# SB_TS_0_53.net
KiCad netlist of a schematic drawn in EAGLE
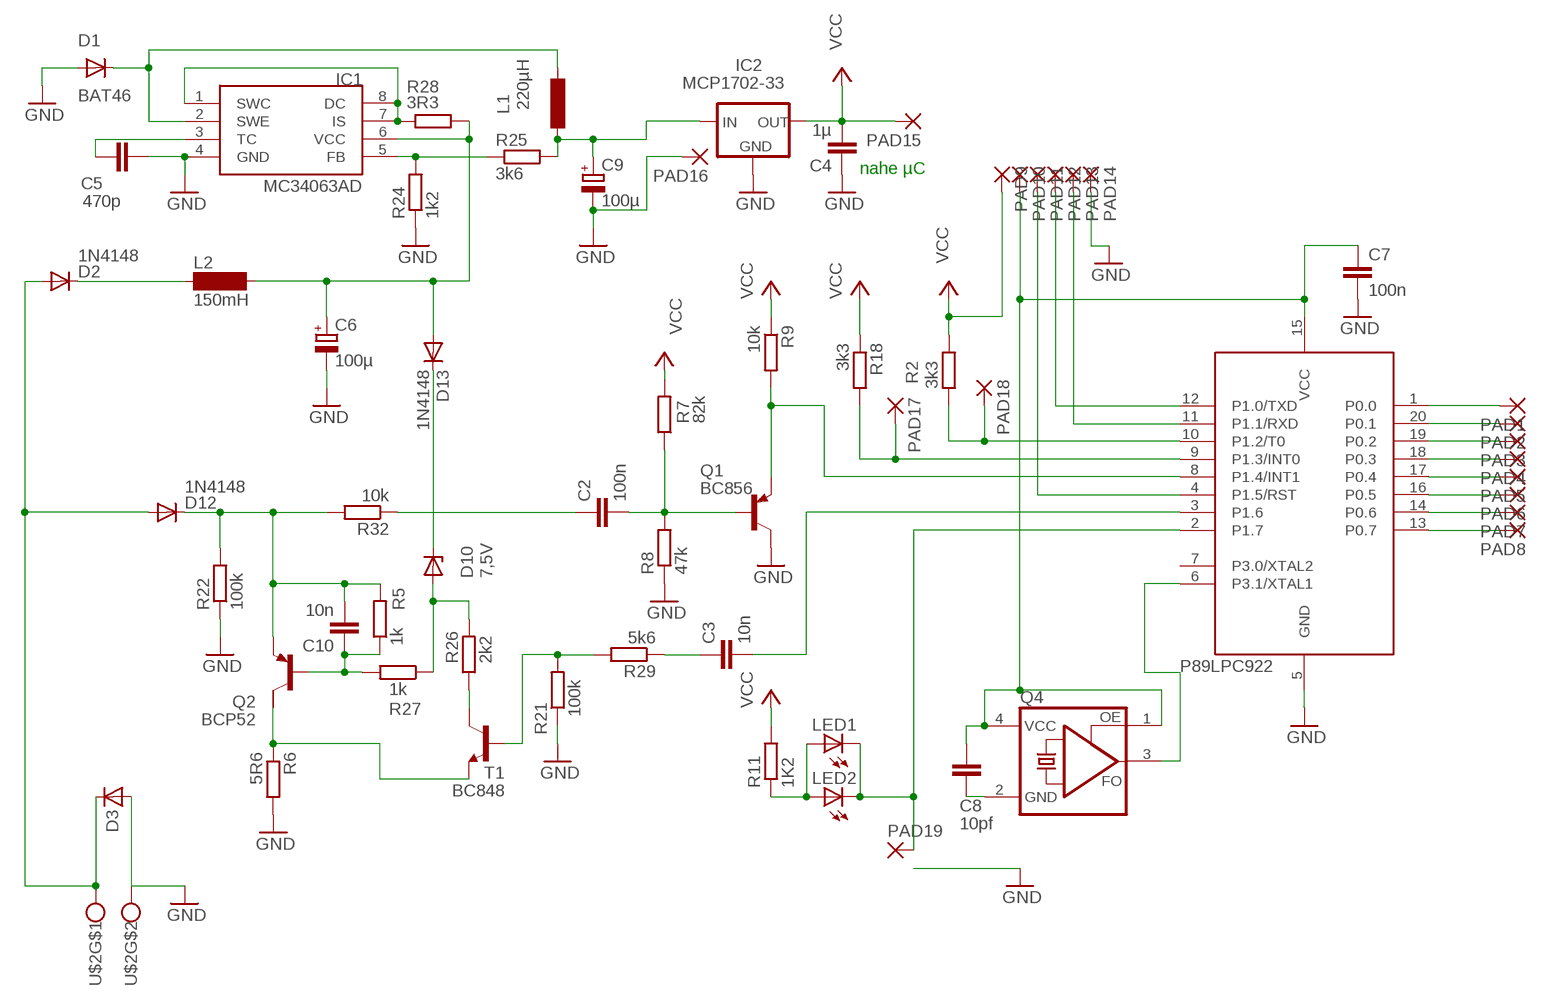
[diagram p0: schematic, sheet 1]

(export (version "E")
  (design (tool "Eeschema 10.0.6"))
  (components
    (comp (ref "C2")
      (value "100n")
      (footprint "eagle-import:C1206")
      (libsource (lib "eagle-import") (part "C-EUC1206"))
    )
    (comp (ref "C3")
      (value "10n")
      (footprint "eagle-import:C1206")
      (libsource (lib "eagle-import") (part "C-EUC1206"))
    )
    (comp (ref "C4")
      (value "1µ")
      (footprint "eagle-import:C1206")
      (libsource (lib "eagle-import") (part "C-EUC1206"))
    )
    (comp (ref "C5")
      (value "470p")
      (footprint "eagle-import:C1206")
      (libsource (lib "eagle-import") (part "C-EUC1206"))
    )
    (comp (ref "C6")
      (value "100µ")
      (footprint "eagle-import:E5-8,5")
      (libsource (lib "eagle-import") (part "CPOL-EUE5-8.5"))
    )
    (comp (ref "C7")
      (value "100n")
      (footprint "eagle-import:C1206")
      (libsource (lib "eagle-import") (part "C-EUC1206"))
    )
    (comp (ref "C8")
      (value "10pf")
      (footprint "eagle-import:C1206")
      (libsource (lib "eagle-import") (part "C-EUC1206"))
    )
    (comp (ref "C9")
      (value "100µ")
      (footprint "eagle-import:E2,5-5")
      (libsource (lib "eagle-import") (part "CPOL-EUE2.5-5"))
    )
    (comp (ref "C10")
      (value "10n")
      (footprint "eagle-import:C1206")
      (libsource (lib "eagle-import") (part "C-EUC1206"))
    )
    (comp (ref "D1")
      (value "BAT46")
      (footprint "eagle-import:MINIMELF")
      (libsource (lib "eagle-import") (part "DIODE-MINIMELF"))
    )
    (comp (ref "D2")
      (value "1N4148")
      (footprint "eagle-import:MINIMELF")
      (libsource (lib "eagle-import") (part "DIODE-MINIMELF"))
    )
    (comp (ref "D3")
      (value "SMAJ40AC")
      (footprint "eagle-import:SMB")
      (libsource (lib "eagle-import") (part "D-SMB"))
    )
    (comp (ref "D10")
      (value "7,5V")
      (footprint "eagle-import:MINIMELF")
      (libsource (lib "eagle-import") (part "ZPD"))
    )
    (comp (ref "D12")
      (value "1N4148")
      (footprint "eagle-import:MINIMELF")
      (libsource (lib "eagle-import") (part "DIODE-MINIMELF"))
    )
    (comp (ref "D13")
      (value "1N4148")
      (footprint "eagle-import:MINIMELF")
      (libsource (lib "eagle-import") (part "DIODE-MINIMELF"))
    )
    (comp (ref "IC1")
      (value "MC34063AD")
      (footprint "eagle-import:SOIC8")
      (libsource (lib "eagle-import") (part "MC34063AD"))
    )
    (comp (ref "IC2")
      (value "MCP1702-33")
      (footprint "eagle-import:79LXX")
      (libsource (lib "eagle-import") (part "79LXX"))
    )
    (comp (ref "L1")
      (value "220µH")
      (footprint "eagle-import:2200-11.43")
      (libsource (lib "eagle-import") (part "L-EU2200-11.43"))
    )
    (comp (ref "L2")
      (value "150mH")
      (footprint "eagle-import:SD12_1000")
      (libsource (lib "eagle-import") (part "SD12-1000"))
    )
    (comp (ref "LED1")
      (value "LEDCHIPLED_1206")
      (footprint "eagle-import:CHIPLED_1206")
      (libsource (lib "eagle-import") (part "LEDCHIPLED_1206"))
    )
    (comp (ref "LED2")
      (value "LED3MM")
      (footprint "eagle-import:LED3MM")
      (libsource (lib "eagle-import") (part "LED3MM"))
    )
    (comp (ref "PAD1")
      (value "SMD2")
      (footprint "eagle-import:SMD1,27-2,54")
      (libsource (lib "eagle-import") (part "SMD2"))
    )
    (comp (ref "PAD2")
      (value "SMD2")
      (footprint "eagle-import:SMD1,27-2,54")
      (libsource (lib "eagle-import") (part "SMD2"))
    )
    (comp (ref "PAD3")
      (value "SMD2")
      (footprint "eagle-import:SMD1,27-2,54")
      (libsource (lib "eagle-import") (part "SMD2"))
    )
    (comp (ref "PAD4")
      (value "SMD2")
      (footprint "eagle-import:SMD1,27-2,54")
      (libsource (lib "eagle-import") (part "SMD2"))
    )
    (comp (ref "PAD5")
      (value "SMD2")
      (footprint "eagle-import:SMD1,27-2,54")
      (libsource (lib "eagle-import") (part "SMD2"))
    )
    (comp (ref "PAD6")
      (value "SMD2")
      (footprint "eagle-import:SMD1,27-2,54")
      (libsource (lib "eagle-import") (part "SMD2"))
    )
    (comp (ref "PAD7")
      (value "SMD2")
      (footprint "eagle-import:SMD1,27-2,54")
      (libsource (lib "eagle-import") (part "SMD2"))
    )
    (comp (ref "PAD8")
      (value "SMD2")
      (footprint "eagle-import:SMD1,27-2,54")
      (libsource (lib "eagle-import") (part "SMD2"))
    )
    (comp (ref "PAD9")
      (value "SMD2")
      (footprint "eagle-import:SMD1,27-2,54")
      (libsource (lib "eagle-import") (part "SMD2"))
    )
    (comp (ref "PAD10")
      (value "SMD2")
      (footprint "eagle-import:SMD1,27-2,54")
      (libsource (lib "eagle-import") (part "SMD2"))
    )
    (comp (ref "PAD11")
      (value "SMD2")
      (footprint "eagle-import:SMD1,27-2,54")
      (libsource (lib "eagle-import") (part "SMD2"))
    )
    (comp (ref "PAD12")
      (value "SMD2")
      (footprint "eagle-import:SMD1,27-2,54")
      (libsource (lib "eagle-import") (part "SMD2"))
    )
    (comp (ref "PAD13")
      (value "SMD2")
      (footprint "eagle-import:SMD1,27-2,54")
      (libsource (lib "eagle-import") (part "SMD2"))
    )
    (comp (ref "PAD14")
      (value "SMD2")
      (footprint "eagle-import:SMD1,27-2,54")
      (libsource (lib "eagle-import") (part "SMD2"))
    )
    (comp (ref "PAD15")
      (value "SMD2")
      (footprint "eagle-import:SMD1,27-2,54")
      (libsource (lib "eagle-import") (part "SMD2"))
    )
    (comp (ref "PAD16")
      (value "SMD2")
      (footprint "eagle-import:SMD1,27-2,54")
      (libsource (lib "eagle-import") (part "SMD2"))
    )
    (comp (ref "PAD17")
      (value "SMD2")
      (footprint "eagle-import:SMD1,27-2,54")
      (libsource (lib "eagle-import") (part "SMD2"))
    )
    (comp (ref "PAD18")
      (value "SMD2")
      (footprint "eagle-import:SMD1,27-2,54")
      (libsource (lib "eagle-import") (part "SMD2"))
    )
    (comp (ref "PAD19")
      (value "SMD2")
      (footprint "eagle-import:SMD1,27-2,54")
      (libsource (lib "eagle-import") (part "SMD2"))
    )
    (comp (ref "Q1")
      (value "BC856")
      (footprint "eagle-import:SOT23-BEC")
      (libsource (lib "eagle-import") (part "BC856SMDALT1"))
    )
    (comp (ref "Q2")
      (value "BCP52")
      (footprint "eagle-import:SOT223")
      (libsource (lib "eagle-import") (part "FZT753SMD"))
    )
    (comp (ref "Q4")
      (value "ASFL")
      (footprint "eagle-import:ASF")
      (libsource (lib "eagle-import") (part "ASFL"))
    )
    (comp (ref "R2")
      (value "3k3")
      (footprint "eagle-import:M1206")
      (libsource (lib "eagle-import") (part "R-EU_M1206"))
    )
    (comp (ref "R5")
      (value "1k")
      (footprint "eagle-import:R1206")
      (libsource (lib "eagle-import") (part "R-EU_R1206"))
    )
    (comp (ref "R6")
      (value "5R6")
      (footprint "eagle-import:R1206")
      (libsource (lib "eagle-import") (part "R-EU_R1206"))
    )
    (comp (ref "R7")
      (value "82k")
      (footprint "eagle-import:R1206")
      (libsource (lib "eagle-import") (part "R-EU_R1206"))
    )
    (comp (ref "R8")
      (value "47k")
      (footprint "eagle-import:M1206")
      (libsource (lib "eagle-import") (part "R-EU_M1206"))
    )
    (comp (ref "R9")
      (value "10k")
      (footprint "eagle-import:R1206")
      (libsource (lib "eagle-import") (part "R-EU_R1206"))
    )
    (comp (ref "R11")
      (value "1K2")
      (footprint "eagle-import:R1206")
      (libsource (lib "eagle-import") (part "R-EU_R1206"))
    )
    (comp (ref "R18")
      (value "3k3")
      (footprint "eagle-import:R1206")
      (libsource (lib "eagle-import") (part "R-EU_R1206"))
    )
    (comp (ref "R21")
      (value "100k")
      (footprint "eagle-import:R1206")
      (libsource (lib "eagle-import") (part "R-EU_R1206"))
    )
    (comp (ref "R22")
      (value "100k")
      (footprint "eagle-import:M1206")
      (libsource (lib "eagle-import") (part "R-EU_M1206"))
    )
    (comp (ref "R24")
      (value "1k2")
      (footprint "eagle-import:R1206")
      (libsource (lib "eagle-import") (part "R-EU_R1206"))
    )
    (comp (ref "R25")
      (value "3k6")
      (footprint "eagle-import:M1206")
      (libsource (lib "eagle-import") (part "R-EU_M1206"))
    )
    (comp (ref "R26")
      (value "2k2")
      (footprint "eagle-import:M1206")
      (libsource (lib "eagle-import") (part "R-EU_M1206"))
    )
    (comp (ref "R27")
      (value "1k")
      (footprint "eagle-import:R1206")
      (libsource (lib "eagle-import") (part "R-EU_R1206"))
    )
    (comp (ref "R28")
      (value "3R3")
      (footprint "eagle-import:M1206")
      (libsource (lib "eagle-import") (part "R-EU_M1206"))
    )
    (comp (ref "R29")
      (value "5k6")
      (footprint "eagle-import:R1206")
      (libsource (lib "eagle-import") (part "R-EU_R1206"))
    )
    (comp (ref "R32")
      (value "10k")
      (footprint "eagle-import:R1206")
      (libsource (lib "eagle-import") (part "R-EU_R1206"))
    )
    (comp (ref "T1")
      (value "BC848")
      (footprint "eagle-import:SOT23")
      (libsource (lib "eagle-import") (part "BC848"))
    )
    (comp (ref "U$2")
      (value "AKL059-02")
      (footprint "eagle-import:AKL3.5X2")
      (libsource (lib "eagle-import") (part "AKL059-02"))
    )
    (comp (ref "U1")
      (value "89LPC922")
      (footprint "eagle-import:DIL20")
      (libsource (lib "eagle-import") (part "89LPC922"))
    )
  )
  (nets
    (net (code "1") (name "GND") (class "Default")
      (node (ref "C4") (pin "1") (pinfunction "1_1") (pintype "passive"))
      (node (ref "C5") (pin "2") (pinfunction "2_2") (pintype "passive"))
      (node (ref "C6") (pin "-") (pinfunction "-_-") (pintype "passive"))
      (node (ref "C7") (pin "2") (pinfunction "2_2") (pintype "passive"))
      (node (ref "C9") (pin "-") (pinfunction "-_-") (pintype "passive"))
      (node (ref "D1") (pin "A") (pinfunction "A_A") (pintype "passive"))
      (node (ref "D3") (pin "2") (pinfunction "A_2") (pintype "passive"))
      (node (ref "IC1") (pin "4") (pinfunction "GND_4") (pintype "passive"))
      (node (ref "IC2") (pin "GND") (pinfunction "GND_GND") (pintype "input"))
      (node (ref "PAD14") (pin "1") (pinfunction "P_1") (pintype "passive"))
      (node (ref "PAD16") (pin "1") (pinfunction "P_1") (pintype "passive"))
      (node (ref "Q1") (pin "C") (pinfunction "C_C") (pintype "passive"))
      (node (ref "R21") (pin "1") (pinfunction "1_1") (pintype "passive"))
      (node (ref "R22") (pin "1") (pinfunction "1_1") (pintype "passive"))
      (node (ref "R24") (pin "1") (pinfunction "1_1") (pintype "passive"))
      (node (ref "R6") (pin "2") (pinfunction "2_2") (pintype "passive"))
      (node (ref "R8") (pin "1") (pinfunction "1_1") (pintype "passive"))
      (node (ref "U$2") (pin "2") (pinfunction "KL_2") (pintype "passive"))
      (node (ref "U1") (pin "5") (pinfunction "GND_5") (pintype "bidirectional"))
    )
    (net (code "2") (name "Net-(C2-Pad1)") (class "Default")
      (node (ref "C2") (pin "1") (pinfunction "1_1") (pintype "passive"))
      (node (ref "R32") (pin "1") (pinfunction "1_1") (pintype "passive"))
    )
    (net (code "3") (name "Net-(C2-Pad2)") (class "Default")
      (node (ref "C2") (pin "2") (pinfunction "2_2") (pintype "passive"))
      (node (ref "Q1") (pin "B") (pinfunction "B_B") (pintype "passive"))
      (node (ref "R7") (pin "1") (pinfunction "1_1") (pintype "passive"))
      (node (ref "R8") (pin "2") (pinfunction "2_2") (pintype "passive"))
    )
    (net (code "4") (name "Net-(C3-Pad1)") (class "Default")
      (node (ref "C3") (pin "1") (pinfunction "1_1") (pintype "passive"))
      (node (ref "R29") (pin "1") (pinfunction "1_1") (pintype "passive"))
    )
    (net (code "5") (name "Net-(C9-Pad+)") (class "Default")
      (node (ref "C9") (pin "+") (pinfunction "+_+") (pintype "passive"))
      (node (ref "IC2") (pin "IN") (pinfunction "IN_IN") (pintype "input"))
      (node (ref "L1") (pin "1") (pinfunction "1_1") (pintype "passive"))
      (node (ref "R25") (pin "2") (pinfunction "2_2") (pintype "passive"))
    )
    (net (code "6") (name "Net-(D2-PadC)") (class "Default")
      (node (ref "D2") (pin "C") (pinfunction "C_C") (pintype "passive"))
      (node (ref "L2") (pin "1") (pinfunction "1_1") (pintype "passive"))
    )
    (net (code "7") (name "Net-(D3-C)") (class "Default")
      (node (ref "D12") (pin "A") (pinfunction "A_A") (pintype "passive"))
      (node (ref "D2") (pin "A") (pinfunction "A_A") (pintype "passive"))
      (node (ref "D3") (pin "1") (pinfunction "C_1") (pintype "passive"))
      (node (ref "U$2") (pin "1") (pinfunction "KL_1") (pintype "passive"))
    )
    (net (code "8") (name "Net-(D10-PadA)") (class "Default")
      (node (ref "D10") (pin "A") (pinfunction "A_A") (pintype "passive"))
      (node (ref "R26") (pin "2") (pinfunction "2_2") (pintype "passive"))
      (node (ref "R27") (pin "1") (pinfunction "1_1") (pintype "passive"))
    )
    (net (code "9") (name "Net-(D10-PadC)") (class "Default")
      (node (ref "D10") (pin "C") (pinfunction "C_C") (pintype "passive"))
      (node (ref "D13") (pin "C") (pinfunction "C_C") (pintype "passive"))
    )
    (net (code "10") (name "Net-(IC1-DC)") (class "Default")
      (node (ref "IC1") (pin "1") (pinfunction "SWC_1") (pintype "passive"))
      (node (ref "IC1") (pin "7") (pinfunction "IS_7") (pintype "passive"))
      (node (ref "IC1") (pin "8") (pinfunction "DC_8") (pintype "passive"))
      (node (ref "R28") (pin "1") (pinfunction "1_1") (pintype "passive"))
    )
    (net (code "11") (name "Net-(IC1-FB)") (class "Default")
      (node (ref "IC1") (pin "5") (pinfunction "FB_5") (pintype "passive"))
      (node (ref "R24") (pin "2") (pinfunction "2_2") (pintype "passive"))
      (node (ref "R25") (pin "1") (pinfunction "1_1") (pintype "passive"))
    )
    (net (code "12") (name "Net-(IC1-SWE)") (class "Default")
      (node (ref "D1") (pin "C") (pinfunction "C_C") (pintype "passive"))
      (node (ref "IC1") (pin "2") (pinfunction "SWE_2") (pintype "passive"))
      (node (ref "L1") (pin "2") (pinfunction "2_2") (pintype "passive"))
    )
    (net (code "13") (name "Net-(IC1-TC)") (class "Default")
      (node (ref "C5") (pin "1") (pinfunction "1_1") (pintype "passive"))
      (node (ref "IC1") (pin "3") (pinfunction "TC_3") (pintype "passive"))
    )
    (net (code "14") (name "Net-(IC1-VCC)") (class "Default")
      (node (ref "C6") (pin "+") (pinfunction "+_+") (pintype "passive"))
      (node (ref "D13") (pin "A") (pinfunction "A_A") (pintype "passive"))
      (node (ref "IC1") (pin "6") (pinfunction "VCC_6") (pintype "passive"))
      (node (ref "L2") (pin "2") (pinfunction "2_2") (pintype "passive"))
      (node (ref "R28") (pin "2") (pinfunction "2_2") (pintype "passive"))
    )
    (net (code "15") (name "Net-(LED1-PadA)") (class "Default")
      (node (ref "LED1") (pin "A") (pinfunction "A_A") (pintype "passive"))
      (node (ref "LED2") (pin "A") (pinfunction "A_A") (pintype "passive"))
      (node (ref "R11") (pin "1") (pinfunction "1_1") (pintype "passive"))
    )
    (net (code "16") (name "Net-(LED2-C)") (class "Default")
      (node (ref "LED1") (pin "C") (pinfunction "C_C") (pintype "passive"))
      (node (ref "LED2") (pin "K") (pinfunction "C_K") (pintype "passive"))
      (node (ref "PAD19") (pin "1") (pinfunction "P_1") (pintype "passive"))
      (node (ref "U1") (pin "2") (pinfunction "P1.7_2") (pintype "bidirectional"))
    )
    (net (code "17") (name "Net-(PAD1-P)") (class "Default")
      (node (ref "PAD1") (pin "1") (pinfunction "P_1") (pintype "passive"))
      (node (ref "U1") (pin "1") (pinfunction "P0.0_1") (pintype "bidirectional"))
    )
    (net (code "18") (name "Net-(PAD2-P)") (class "Default")
      (node (ref "PAD2") (pin "1") (pinfunction "P_1") (pintype "passive"))
      (node (ref "U1") (pin "20") (pinfunction "P0.1_20") (pintype "bidirectional"))
    )
    (net (code "19") (name "Net-(PAD3-P)") (class "Default")
      (node (ref "PAD3") (pin "1") (pinfunction "P_1") (pintype "passive"))
      (node (ref "U1") (pin "19") (pinfunction "P0.2_19") (pintype "bidirectional"))
    )
    (net (code "20") (name "Net-(PAD4-P)") (class "Default")
      (node (ref "PAD4") (pin "1") (pinfunction "P_1") (pintype "passive"))
      (node (ref "U1") (pin "18") (pinfunction "P0.3_18") (pintype "bidirectional"))
    )
    (net (code "21") (name "Net-(PAD5-P)") (class "Default")
      (node (ref "PAD5") (pin "1") (pinfunction "P_1") (pintype "passive"))
      (node (ref "U1") (pin "17") (pinfunction "P0.4_17") (pintype "bidirectional"))
    )
    (net (code "22") (name "Net-(PAD6-P)") (class "Default")
      (node (ref "PAD6") (pin "1") (pinfunction "P_1") (pintype "passive"))
      (node (ref "U1") (pin "16") (pinfunction "P0.5_16") (pintype "bidirectional"))
    )
    (net (code "23") (name "Net-(PAD7-P)") (class "Default")
      (node (ref "PAD7") (pin "1") (pinfunction "P_1") (pintype "passive"))
      (node (ref "U1") (pin "14") (pinfunction "P0.6_14") (pintype "bidirectional"))
    )
    (net (code "24") (name "Net-(PAD8-P)") (class "Default")
      (node (ref "PAD8") (pin "1") (pinfunction "P_1") (pintype "passive"))
      (node (ref "U1") (pin "13") (pinfunction "P0.7_13") (pintype "bidirectional"))
    )
    (net (code "25") (name "Net-(PAD10-P)") (class "Default")
      (node (ref "C7") (pin "1") (pinfunction "1_1") (pintype "passive"))
      (node (ref "C8") (pin "1") (pinfunction "1_1") (pintype "passive"))
      (node (ref "PAD10") (pin "1") (pinfunction "P_1") (pintype "passive"))
      (node (ref "Q4") (pin "1") (pinfunction "OE_1") (pintype "input"))
      (node (ref "Q4") (pin "4") (pinfunction "VCC_4") (pintype "power_in"))
      (node (ref "U1") (pin "15") (pinfunction "VCC_15") (pintype "bidirectional"))
    )
    (net (code "26") (name "Net-(PAD11-P)") (class "Default")
      (node (ref "PAD11") (pin "1") (pinfunction "P_1") (pintype "passive"))
      (node (ref "U1") (pin "4") (pinfunction "P1.5/RST_4") (pintype "bidirectional"))
    )
    (net (code "27") (name "Net-(PAD12-P)") (class "Default")
      (node (ref "PAD12") (pin "1") (pinfunction "P_1") (pintype "passive"))
      (node (ref "U1") (pin "12") (pinfunction "P1.0/TXD_12") (pintype "bidirectional"))
    )
    (net (code "28") (name "Net-(PAD13-P)") (class "Default")
      (node (ref "PAD13") (pin "1") (pinfunction "P_1") (pintype "passive"))
      (node (ref "U1") (pin "11") (pinfunction "P1.1/RXD_11") (pintype "bidirectional"))
    )
    (net (code "29") (name "Net-(PAD17-P)") (class "Default")
      (node (ref "PAD17") (pin "1") (pinfunction "P_1") (pintype "passive"))
      (node (ref "R18") (pin "2") (pinfunction "2_2") (pintype "passive"))
      (node (ref "U1") (pin "9") (pinfunction "P1.3/INT0_9") (pintype "bidirectional"))
    )
    (net (code "30") (name "Net-(PAD18-P)") (class "Default")
      (node (ref "PAD18") (pin "1") (pinfunction "P_1") (pintype "passive"))
      (node (ref "R2") (pin "2") (pinfunction "2_2") (pintype "passive"))
      (node (ref "U1") (pin "10") (pinfunction "P1.2/T0_10") (pintype "bidirectional"))
    )
    (net (code "31") (name "Net-(Q2-B)") (class "Default")
      (node (ref "C10") (pin "1") (pinfunction "1_1") (pintype "passive"))
      (node (ref "Q2") (pin "1") (pinfunction "B_1") (pintype "passive"))
      (node (ref "R27") (pin "2") (pinfunction "2_2") (pintype "passive"))
      (node (ref "R5") (pin "1") (pinfunction "1_1") (pintype "passive"))
    )
    (net (code "32") (name "Net-(Q2-C)") (class "Default")
      (node (ref "Q2") (pin "2") (pinfunction "C_2") (pintype "passive"))
      (node (ref "R6") (pin "1") (pinfunction "1_1") (pintype "passive"))
      (node (ref "T1") (pin "2") (pinfunction "E_2") (pintype "passive"))
    )
    (net (code "33") (name "Net-(Q2-E)") (class "Default")
      (node (ref "C10") (pin "2") (pinfunction "2_2") (pintype "passive"))
      (node (ref "D12") (pin "C") (pinfunction "C_C") (pintype "passive"))
      (node (ref "Q2") (pin "3") (pinfunction "E_3") (pintype "passive"))
      (node (ref "R22") (pin "2") (pinfunction "2_2") (pintype "passive"))
      (node (ref "R32") (pin "2") (pinfunction "2_2") (pintype "passive"))
      (node (ref "R5") (pin "2") (pinfunction "2_2") (pintype "passive"))
    )
    (net (code "34") (name "Net-(Q4-FO)") (class "Default")
      (node (ref "Q4") (pin "3") (pinfunction "FO_3") (pintype "output"))
      (node (ref "U1") (pin "6") (pinfunction "P3.1/XTAL1_6") (pintype "bidirectional"))
    )
    (net (code "35") (name "Net-(Q4-GND)") (class "Default")
      (node (ref "C8") (pin "2") (pinfunction "2_2") (pintype "passive"))
      (node (ref "Q4") (pin "2") (pinfunction "GND_2") (pintype "power_in"))
    )
    (net (code "36") (name "Net-(T1-B)") (class "Default")
      (node (ref "R21") (pin "2") (pinfunction "2_2") (pintype "passive"))
      (node (ref "R29") (pin "2") (pinfunction "2_2") (pintype "passive"))
      (node (ref "T1") (pin "1") (pinfunction "B_1") (pintype "passive"))
    )
    (net (code "37") (name "Net-(T1-C)") (class "Default")
      (node (ref "R26") (pin "1") (pinfunction "1_1") (pintype "passive"))
      (node (ref "T1") (pin "3") (pinfunction "C_3") (pintype "passive"))
    )
    (net (code "38") (name "Net-(U1-P1.4{slash}INT1)") (class "Default")
      (node (ref "Q1") (pin "E") (pinfunction "E_E") (pintype "passive"))
      (node (ref "R9") (pin "2") (pinfunction "2_2") (pintype "passive"))
      (node (ref "U1") (pin "8") (pinfunction "P1.4/INT1_8") (pintype "bidirectional"))
    )
    (net (code "39") (name "Net-(U1-P1.6)") (class "Default")
      (node (ref "C3") (pin "2") (pinfunction "2_2") (pintype "passive"))
      (node (ref "U1") (pin "3") (pinfunction "P1.6_3") (pintype "bidirectional"))
    )
    (net (code "40") (name "VCC") (class "Default")
      (node (ref "C4") (pin "2") (pinfunction "2_2") (pintype "passive"))
      (node (ref "IC2") (pin "OUT") (pinfunction "OUT_OUT") (pintype "passive"))
      (node (ref "PAD15") (pin "1") (pinfunction "P_1") (pintype "passive"))
      (node (ref "PAD9") (pin "1") (pinfunction "P_1") (pintype "passive"))
      (node (ref "R11") (pin "2") (pinfunction "2_2") (pintype "passive"))
      (node (ref "R18") (pin "1") (pinfunction "1_1") (pintype "passive"))
      (node (ref "R2") (pin "1") (pinfunction "1_1") (pintype "passive"))
      (node (ref "R7") (pin "2") (pinfunction "2_2") (pintype "passive"))
      (node (ref "R9") (pin "1") (pinfunction "1_1") (pintype "passive"))
    )
    (net (code "41") (name "unconnected-(Q2-C{slash}-Pad4)") (class "Default")
      (node (ref "Q2") (pin "4") (pinfunction "C/_4") (pintype "passive"))
    )
    (net (code "42") (name "unconnected-(U1-P3.0{slash}XTAL2-Pad7)") (class "Default")
      (node (ref "U1") (pin "7") (pinfunction "P3.0/XTAL2_7") (pintype "bidirectional"))
    )
  )
)
